# NT_SolarModule.net
KiCad netlist of a schematic drawn in EAGLE
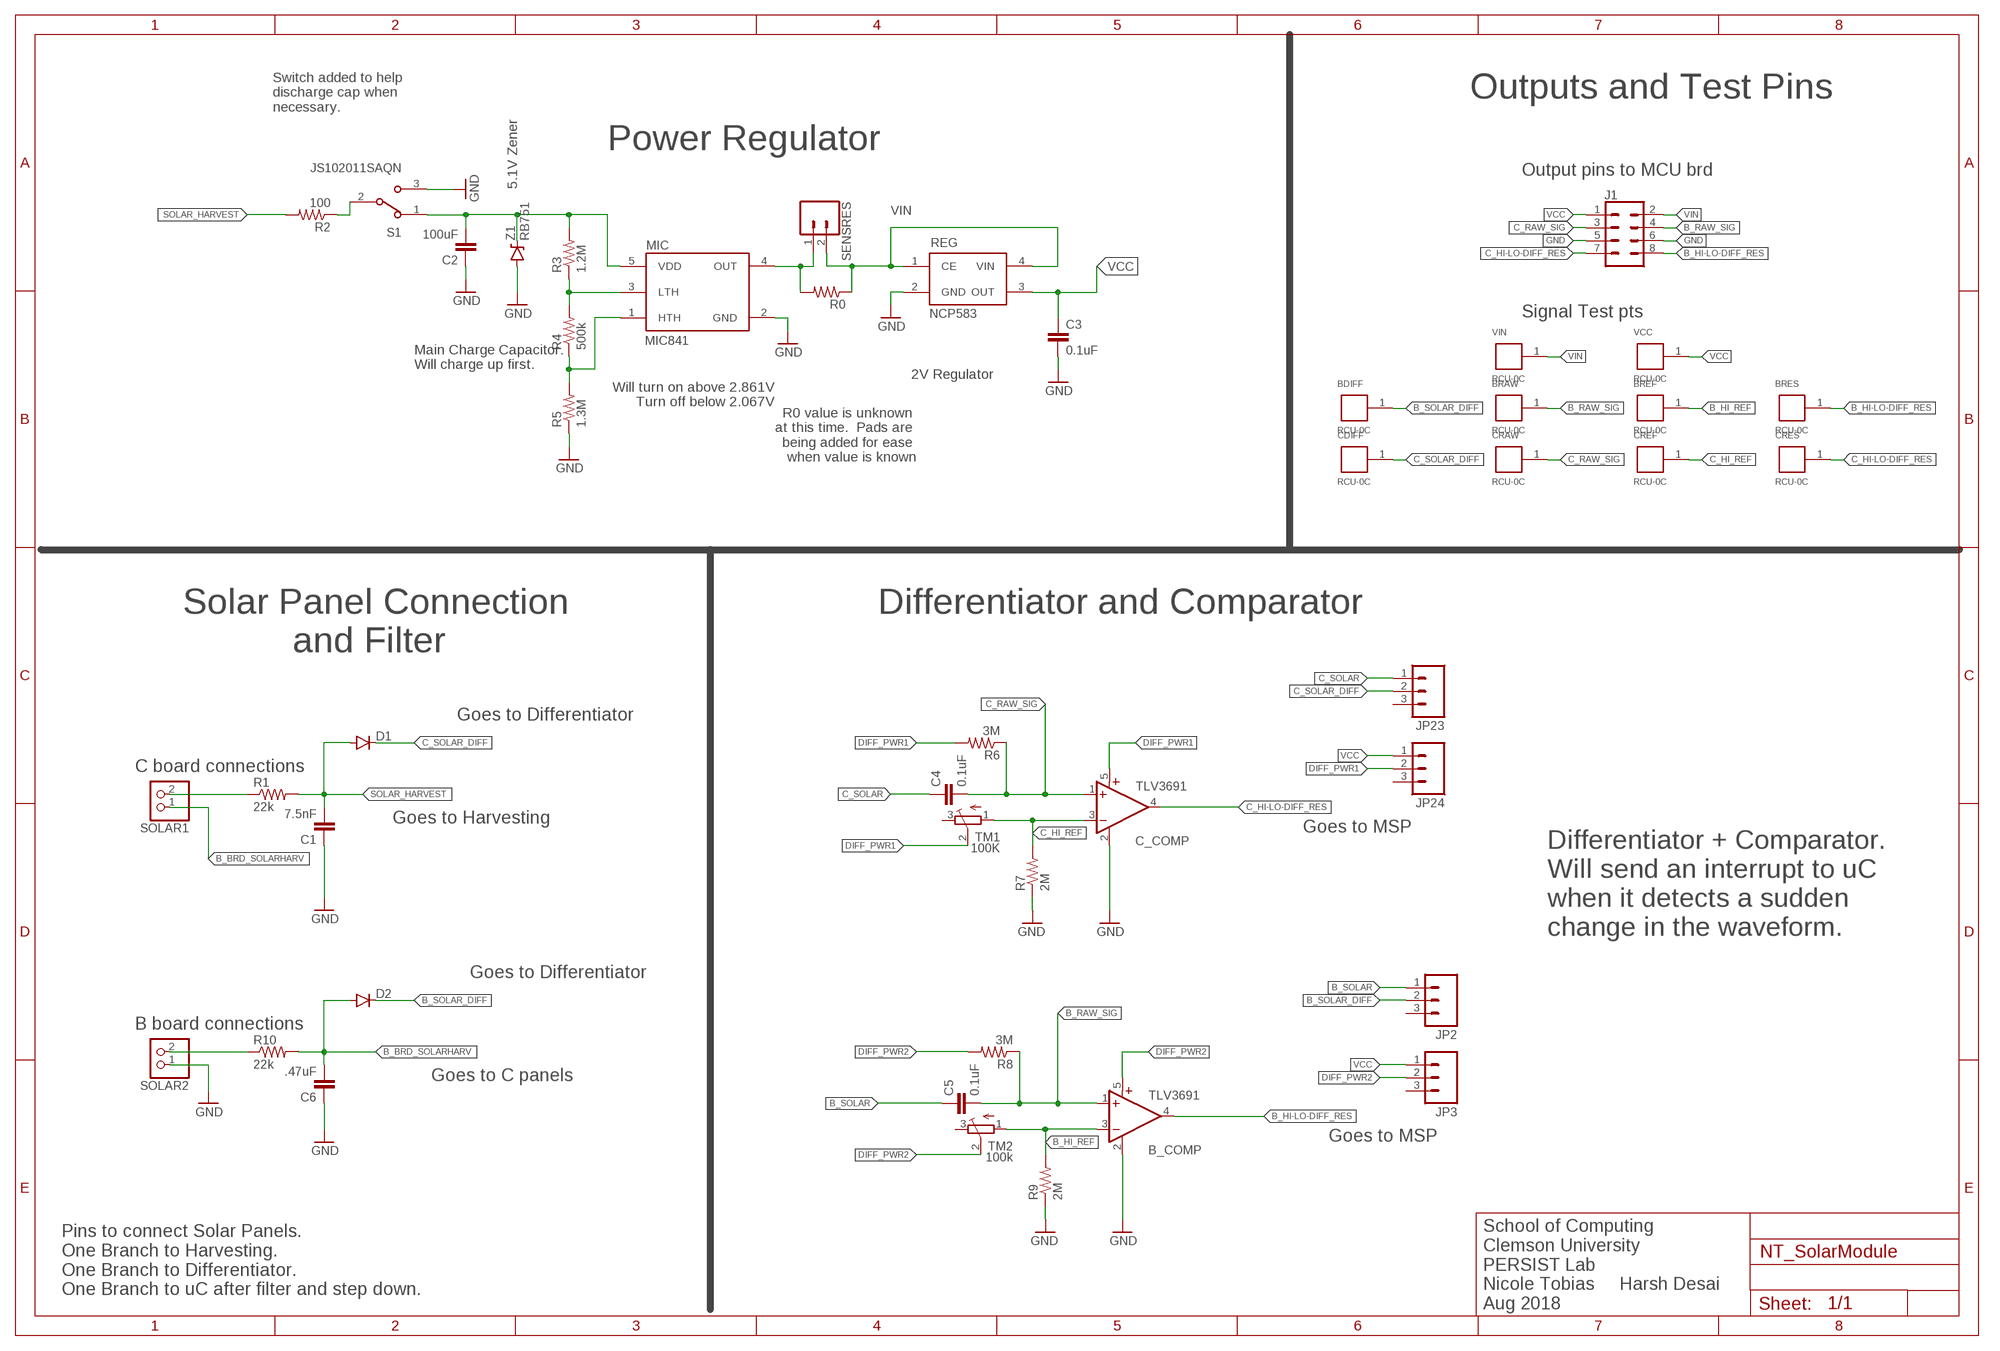
[diagram p0: schematic, sheet 1]

(export (version "E")
  (design (tool "Eeschema 10.0.6"))
  (components
    (comp (ref "BDIFF")
      (value "RCU-0C")
      (footprint "eagle-import:TE_RCU-0C")
      (fields
        (field (name "COMMENT") "RCU-0C _1625854-3_")
        (field (name "MF") "TE Connectivity")
        (field (name "TOLERANCE") "0%")
      )
      (libsource (lib "eagle-import") (part "RCU-0C"))
    )
    (comp (ref "BRAW")
      (value "RCU-0C")
      (footprint "eagle-import:TE_RCU-0C")
      (fields
        (field (name "COMMENT") "RCU-0C _1625854-3_")
        (field (name "MF") "TE Connectivity")
        (field (name "TOLERANCE") "0%")
      )
      (libsource (lib "eagle-import") (part "RCU-0C"))
    )
    (comp (ref "BREF")
      (value "RCU-0C")
      (footprint "eagle-import:TE_RCU-0C")
      (fields
        (field (name "COMMENT") "RCU-0C _1625854-3_")
        (field (name "MF") "TE Connectivity")
        (field (name "TOLERANCE") "0%")
      )
      (libsource (lib "eagle-import") (part "RCU-0C"))
    )
    (comp (ref "BRES")
      (value "RCU-0C")
      (footprint "eagle-import:TE_RCU-0C")
      (fields
        (field (name "COMMENT") "RCU-0C _1625854-3_")
        (field (name "MF") "TE Connectivity")
        (field (name "TOLERANCE") "0%")
      )
      (libsource (lib "eagle-import") (part "RCU-0C"))
    )
    (comp (ref "B_COMP")
      (value "TLV3691")
      (footprint "eagle-import:SC70-5")
      (libsource (lib "eagle-import") (part "TLV3691"))
    )
    (comp (ref "C1")
      (value "7.5nF")
      (footprint "eagle-import:0603-CAP")
      (libsource (lib "eagle-import") (part "CAP0603-CAP"))
    )
    (comp (ref "C2")
      (value "100uF")
      (footprint "eagle-import:0603-CAP")
      (libsource (lib "eagle-import") (part "CAP0603-CAP"))
    )
    (comp (ref "C3")
      (value "0.1uF")
      (footprint "eagle-import:0603-CAP")
      (libsource (lib "eagle-import") (part "CAP0603-CAP"))
    )
    (comp (ref "C4")
      (value "0.1uF")
      (footprint "eagle-import:0603-CAP")
      (libsource (lib "eagle-import") (part "CAP0603-CAP"))
    )
    (comp (ref "C5")
      (value "0.1uF")
      (footprint "eagle-import:0603-CAP")
      (libsource (lib "eagle-import") (part "CAP0603-CAP"))
    )
    (comp (ref "C6")
      (value ".47uF")
      (footprint "eagle-import:0603-CAP")
      (libsource (lib "eagle-import") (part "CAP0603-CAP"))
    )
    (comp (ref "CDIFF")
      (value "RCU-0C")
      (footprint "eagle-import:TE_RCU-0C")
      (fields
        (field (name "COMMENT") "RCU-0C _1625854-3_")
        (field (name "MF") "TE Connectivity")
        (field (name "TOLERANCE") "0%")
      )
      (libsource (lib "eagle-import") (part "RCU-0C"))
    )
    (comp (ref "CRAW")
      (value "RCU-0C")
      (footprint "eagle-import:TE_RCU-0C")
      (fields
        (field (name "COMMENT") "RCU-0C _1625854-3_")
        (field (name "MF") "TE Connectivity")
        (field (name "TOLERANCE") "0%")
      )
      (libsource (lib "eagle-import") (part "RCU-0C"))
    )
    (comp (ref "CREF")
      (value "RCU-0C")
      (footprint "eagle-import:TE_RCU-0C")
      (fields
        (field (name "COMMENT") "RCU-0C _1625854-3_")
        (field (name "MF") "TE Connectivity")
        (field (name "TOLERANCE") "0%")
      )
      (libsource (lib "eagle-import") (part "RCU-0C"))
    )
    (comp (ref "CRES")
      (value "RCU-0C")
      (footprint "eagle-import:TE_RCU-0C")
      (fields
        (field (name "COMMENT") "RCU-0C _1625854-3_")
        (field (name "MF") "TE Connectivity")
        (field (name "TOLERANCE") "0%")
      )
      (libsource (lib "eagle-import") (part "RCU-0C"))
    )
    (comp (ref "C_COMP")
      (value "TLV3691")
      (footprint "eagle-import:SC70-5")
      (libsource (lib "eagle-import") (part "TLV3691"))
    )
    (comp (ref "D1")
      (value "DIODESOD523")
      (footprint "eagle-import:SOD523")
      (libsource (lib "eagle-import") (part "DIODESOD523"))
    )
    (comp (ref "D2")
      (value "DIODESOD523")
      (footprint "eagle-import:SOD523")
      (libsource (lib "eagle-import") (part "DIODESOD523"))
    )
    (comp (ref "J1")
      (value "CONN_04X2")
      (footprint "eagle-import:2X4")
      (libsource (lib "eagle-import") (part "CONN_04X2"))
    )
    (comp (ref "JP2")
      (value "M03")
      (footprint "eagle-import:1X03-1.27MM")
      (libsource (lib "eagle-import") (part "M03"))
    )
    (comp (ref "JP3")
      (value "M03")
      (footprint "eagle-import:1X03-1.27MM")
      (libsource (lib "eagle-import") (part "M03"))
    )
    (comp (ref "JP23")
      (value "M03")
      (footprint "eagle-import:1X03-1.27MM")
      (libsource (lib "eagle-import") (part "M03"))
    )
    (comp (ref "JP24")
      (value "M03")
      (footprint "eagle-import:1X03-1.27MM")
      (libsource (lib "eagle-import") (part "M03"))
    )
    (comp (ref "MIC")
      (value "MIC841")
      (footprint "eagle-import:SC70-5")
      (libsource (lib "eagle-import") (part "MIC841"))
    )
    (comp (ref "R0")
      (value "RESISTOR0603")
      (footprint "eagle-import:0603-RES")
      (libsource (lib "eagle-import") (part "RESISTOR0603"))
    )
    (comp (ref "R1")
      (value "22k")
      (footprint "eagle-import:0603-RES")
      (libsource (lib "eagle-import") (part "RESISTOR0603"))
    )
    (comp (ref "R2")
      (value "100")
      (footprint "eagle-import:0603-RES")
      (libsource (lib "eagle-import") (part "RESISTOR0603"))
    )
    (comp (ref "R3")
      (value "1.2M")
      (footprint "eagle-import:0603-RES")
      (libsource (lib "eagle-import") (part "RESISTOR0603"))
    )
    (comp (ref "R4")
      (value "500k")
      (footprint "eagle-import:0603-RES")
      (libsource (lib "eagle-import") (part "RESISTOR0603"))
    )
    (comp (ref "R5")
      (value "1.3M")
      (footprint "eagle-import:0603-RES")
      (libsource (lib "eagle-import") (part "RESISTOR0603"))
    )
    (comp (ref "R6")
      (value "3M")
      (footprint "eagle-import:0603-RES")
      (libsource (lib "eagle-import") (part "RESISTOR0603"))
    )
    (comp (ref "R7")
      (value "2M")
      (footprint "eagle-import:0603-RES")
      (libsource (lib "eagle-import") (part "RESISTOR0603"))
    )
    (comp (ref "R8")
      (value "3M")
      (footprint "eagle-import:0603-RES")
      (libsource (lib "eagle-import") (part "RESISTOR0603"))
    )
    (comp (ref "R9")
      (value "2M")
      (footprint "eagle-import:0603-RES")
      (libsource (lib "eagle-import") (part "RESISTOR0603"))
    )
    (comp (ref "R10")
      (value "22k")
      (footprint "eagle-import:0603-RES")
      (libsource (lib "eagle-import") (part "RESISTOR0603"))
    )
    (comp (ref "REG")
      (value "NCP583")
      (footprint "eagle-import:SC82-AB_1PRIMARY")
      (libsource (lib "eagle-import") (part "NCP583"))
    )
    (comp (ref "S1")
      (value "JS102011SAQN")
      (footprint "eagle-import:SW_JS102011SAQN")
      (fields (field (name "MF") "C&K Components"))
      (libsource (lib "eagle-import") (part "JS102011SAQN"))
    )
    (comp (ref "SENSRES")
      (value "CONN_02")
      (footprint "eagle-import:1X02")
      (libsource (lib "eagle-import") (part "CONN_02"))
    )
    (comp (ref "SOLAR1")
      (value "PINHD-1X2")
      (footprint "eagle-import:1X02")
      (libsource (lib "eagle-import") (part "PINHD-1X2"))
    )
    (comp (ref "SOLAR2")
      (value "PINHD-1X2")
      (footprint "eagle-import:1X02")
      (libsource (lib "eagle-import") (part "PINHD-1X2"))
    )
    (comp (ref "TM1")
      (value "100K")
      (footprint "eagle-import:TC33X")
      (libsource (lib "eagle-import") (part "TRIMPOTTC33X"))
    )
    (comp (ref "TM2")
      (value "100k")
      (footprint "eagle-import:TC33X")
      (libsource (lib "eagle-import") (part "TRIMPOTTC33X"))
    )
    (comp (ref "VCC")
      (value "RCU-0C")
      (footprint "eagle-import:TE_RCU-0C")
      (fields
        (field (name "COMMENT") "RCU-0C _1625854-3_")
        (field (name "MF") "TE Connectivity")
        (field (name "TOLERANCE") "0%")
      )
      (libsource (lib "eagle-import") (part "RCU-0C"))
    )
    (comp (ref "VIN")
      (value "RCU-0C")
      (footprint "eagle-import:TE_RCU-0C")
      (fields
        (field (name "COMMENT") "RCU-0C _1625854-3_")
        (field (name "MF") "TE Connectivity")
        (field (name "TOLERANCE") "0%")
      )
      (libsource (lib "eagle-import") (part "RCU-0C"))
    )
    (comp (ref "Z1")
      (value "RB751")
      (footprint "eagle-import:SOD-523")
      (libsource (lib "eagle-import") (part "DIODE-ZENER"))
    )
  )
  (nets
    (net (code "1") (name "B_BRD_SOLARHARV") (class "Default")
      (node (ref "C6") (pin "2") (pinfunction "2_2") (pintype "passive"))
      (node (ref "D2") (pin "A") (pinfunction "A_A") (pintype "passive"))
      (node (ref "R10") (pin "2") (pinfunction "2_2") (pintype "passive"))
      (node (ref "SOLAR1") (pin "1") (pinfunction "1_1") (pintype "passive"))
    )
    (net (code "2") (name "B_HI-LO-DIFF_RES") (class "Default")
      (node (ref "BRES") (pin "1") (pinfunction "1_1") (pintype "passive"))
      (node (ref "B_COMP") (pin "4") (pinfunction "OUT_4") (pintype "output"))
      (node (ref "J1") (pin "8") (pinfunction "8_8") (pintype "passive"))
    )
    (net (code "3") (name "B_HI_REF") (class "Default")
      (node (ref "BREF") (pin "1") (pinfunction "1_1") (pintype "passive"))
      (node (ref "B_COMP") (pin "3") (pinfunction "-IN_3") (pintype "input"))
      (node (ref "R9") (pin "2") (pinfunction "2_2") (pintype "passive"))
      (node (ref "TM2") (pin "1") (pinfunction "A_1") (pintype "passive"))
    )
    (net (code "4") (name "B_RAW_SIG") (class "Default")
      (node (ref "BRAW") (pin "1") (pinfunction "1_1") (pintype "passive"))
      (node (ref "B_COMP") (pin "1") (pinfunction "+IN_1") (pintype "input"))
      (node (ref "C5") (pin "2") (pinfunction "2_2") (pintype "passive"))
      (node (ref "J1") (pin "4") (pinfunction "4_4") (pintype "passive"))
      (node (ref "R8") (pin "1") (pinfunction "1_1") (pintype "passive"))
    )
    (net (code "5") (name "B_SOLAR") (class "Default")
      (node (ref "C5") (pin "1") (pinfunction "1_1") (pintype "passive"))
      (node (ref "JP2") (pin "1") (pinfunction "1_1") (pintype "passive"))
    )
    (net (code "6") (name "B_SOLAR_DIFF") (class "Default")
      (node (ref "BDIFF") (pin "1") (pinfunction "1_1") (pintype "passive"))
      (node (ref "D2") (pin "C") (pinfunction "C_C") (pintype "passive"))
      (node (ref "JP2") (pin "2") (pinfunction "2_2") (pintype "passive"))
    )
    (net (code "7") (name "C_HI-LO-DIFF_RES") (class "Default")
      (node (ref "CRES") (pin "1") (pinfunction "1_1") (pintype "passive"))
      (node (ref "C_COMP") (pin "4") (pinfunction "OUT_4") (pintype "output"))
      (node (ref "J1") (pin "7") (pinfunction "7_7") (pintype "passive"))
    )
    (net (code "8") (name "C_HI_REF") (class "Default")
      (node (ref "CREF") (pin "1") (pinfunction "1_1") (pintype "passive"))
      (node (ref "C_COMP") (pin "3") (pinfunction "-IN_3") (pintype "input"))
      (node (ref "R7") (pin "2") (pinfunction "2_2") (pintype "passive"))
      (node (ref "TM1") (pin "1") (pinfunction "A_1") (pintype "passive"))
    )
    (net (code "9") (name "C_RAW_SIG") (class "Default")
      (node (ref "C4") (pin "2") (pinfunction "2_2") (pintype "passive"))
      (node (ref "CRAW") (pin "1") (pinfunction "1_1") (pintype "passive"))
      (node (ref "C_COMP") (pin "1") (pinfunction "+IN_1") (pintype "input"))
      (node (ref "J1") (pin "3") (pinfunction "3_3") (pintype "passive"))
      (node (ref "R6") (pin "1") (pinfunction "1_1") (pintype "passive"))
    )
    (net (code "10") (name "C_SOLAR") (class "Default")
      (node (ref "C4") (pin "1") (pinfunction "1_1") (pintype "passive"))
      (node (ref "JP23") (pin "1") (pinfunction "1_1") (pintype "passive"))
    )
    (net (code "11") (name "C_SOLAR_DIFF") (class "Default")
      (node (ref "CDIFF") (pin "1") (pinfunction "1_1") (pintype "passive"))
      (node (ref "D1") (pin "C") (pinfunction "C_C") (pintype "passive"))
      (node (ref "JP23") (pin "2") (pinfunction "2_2") (pintype "passive"))
    )
    (net (code "12") (name "DIFF_PWR1") (class "Default")
      (node (ref "C_COMP") (pin "5") (pinfunction "V+_5") (pintype "power_in"))
      (node (ref "JP24") (pin "2") (pinfunction "2_2") (pintype "passive"))
      (node (ref "R6") (pin "2") (pinfunction "2_2") (pintype "passive"))
      (node (ref "TM1") (pin "2") (pinfunction "S_2") (pintype "passive"))
    )
    (net (code "13") (name "DIFF_PWR2") (class "Default")
      (node (ref "B_COMP") (pin "5") (pinfunction "V+_5") (pintype "power_in"))
      (node (ref "JP3") (pin "2") (pinfunction "2_2") (pintype "passive"))
      (node (ref "R8") (pin "2") (pinfunction "2_2") (pintype "passive"))
      (node (ref "TM2") (pin "2") (pinfunction "S_2") (pintype "passive"))
    )
    (net (code "14") (name "GND") (class "Default")
      (node (ref "B_COMP") (pin "2") (pinfunction "GND_2") (pintype "power_in"))
      (node (ref "C1") (pin "1") (pinfunction "1_1") (pintype "passive"))
      (node (ref "C2") (pin "1") (pinfunction "1_1") (pintype "passive"))
      (node (ref "C3") (pin "2") (pinfunction "2_2") (pintype "passive"))
      (node (ref "C6") (pin "1") (pinfunction "1_1") (pintype "passive"))
      (node (ref "C_COMP") (pin "2") (pinfunction "GND_2") (pintype "power_in"))
      (node (ref "J1") (pin "5") (pinfunction "5_5") (pintype "passive"))
      (node (ref "J1") (pin "6") (pinfunction "6_6") (pintype "passive"))
      (node (ref "MIC") (pin "2") (pinfunction "GND_2") (pintype "bidirectional"))
      (node (ref "R5") (pin "1") (pinfunction "1_1") (pintype "passive"))
      (node (ref "R7") (pin "1") (pinfunction "1_1") (pintype "passive"))
      (node (ref "R9") (pin "1") (pinfunction "1_1") (pintype "passive"))
      (node (ref "REG") (pin "2") (pinfunction "GND_2") (pintype "bidirectional"))
      (node (ref "S1") (pin "3") (pinfunction "3_3") (pintype "passive"))
      (node (ref "SOLAR2") (pin "1") (pinfunction "1_1") (pintype "passive"))
      (node (ref "Z1") (pin "ANODE") (pinfunction "A_ANODE") (pintype "passive"))
    )
    (net (code "15") (name "Net-(MIC-HTH)") (class "Default")
      (node (ref "MIC") (pin "1") (pinfunction "HTH_1") (pintype "bidirectional"))
      (node (ref "R4") (pin "1") (pinfunction "1_1") (pintype "passive"))
      (node (ref "R5") (pin "2") (pinfunction "2_2") (pintype "passive"))
    )
    (net (code "16") (name "Net-(MIC-LTH)") (class "Default")
      (node (ref "MIC") (pin "3") (pinfunction "LTH_3") (pintype "bidirectional"))
      (node (ref "R3") (pin "1") (pinfunction "1_1") (pintype "passive"))
      (node (ref "R4") (pin "2") (pinfunction "2_2") (pintype "passive"))
    )
    (net (code "17") (name "Net-(MIC-OUT)") (class "Default")
      (node (ref "MIC") (pin "4") (pinfunction "OUT_4") (pintype "bidirectional"))
      (node (ref "R0") (pin "2") (pinfunction "2_2") (pintype "passive"))
      (node (ref "SENSRES") (pin "1") (pinfunction "1_1") (pintype "passive"))
    )
    (net (code "18") (name "Net-(MIC-VDD)") (class "Default")
      (node (ref "C2") (pin "2") (pinfunction "2_2") (pintype "passive"))
      (node (ref "MIC") (pin "5") (pinfunction "VDD_5") (pintype "bidirectional"))
      (node (ref "R3") (pin "2") (pinfunction "2_2") (pintype "passive"))
      (node (ref "S1") (pin "1") (pinfunction "1_1") (pintype "passive"))
      (node (ref "Z1") (pin "CATHODE") (pinfunction "C_CATHODE") (pintype "passive"))
    )
    (net (code "19") (name "Net-(R1-Pad1)") (class "Default")
      (node (ref "R1") (pin "1") (pinfunction "1_1") (pintype "passive"))
      (node (ref "SOLAR1") (pin "2") (pinfunction "2_2") (pintype "passive"))
    )
    (net (code "20") (name "Net-(R2-Pad1)") (class "Default")
      (node (ref "R2") (pin "1") (pinfunction "1_1") (pintype "passive"))
      (node (ref "S1") (pin "2") (pinfunction "2_2") (pintype "passive"))
    )
    (net (code "21") (name "Net-(R10-Pad1)") (class "Default")
      (node (ref "R10") (pin "1") (pinfunction "1_1") (pintype "passive"))
      (node (ref "SOLAR2") (pin "2") (pinfunction "2_2") (pintype "passive"))
    )
    (net (code "22") (name "SOLAR_HARVEST") (class "Default")
      (node (ref "C1") (pin "2") (pinfunction "2_2") (pintype "passive"))
      (node (ref "D1") (pin "A") (pinfunction "A_A") (pintype "passive"))
      (node (ref "R1") (pin "2") (pinfunction "2_2") (pintype "passive"))
      (node (ref "R2") (pin "2") (pinfunction "2_2") (pintype "passive"))
    )
    (net (code "23") (name "VCC") (class "Default")
      (node (ref "C3") (pin "1") (pinfunction "1_1") (pintype "passive"))
      (node (ref "J1") (pin "1") (pinfunction "1_1") (pintype "passive"))
      (node (ref "JP24") (pin "1") (pinfunction "1_1") (pintype "passive"))
      (node (ref "JP3") (pin "1") (pinfunction "1_1") (pintype "passive"))
      (node (ref "REG") (pin "3") (pinfunction "OUT_3") (pintype "bidirectional"))
      (node (ref "VCC") (pin "1") (pinfunction "1_1") (pintype "passive"))
    )
    (net (code "24") (name "VIN") (class "Default")
      (node (ref "J1") (pin "2") (pinfunction "2_2") (pintype "passive"))
      (node (ref "R0") (pin "1") (pinfunction "1_1") (pintype "passive"))
      (node (ref "REG") (pin "1") (pinfunction "CE_1") (pintype "bidirectional"))
      (node (ref "REG") (pin "4") (pinfunction "VIN_4") (pintype "bidirectional"))
      (node (ref "SENSRES") (pin "2") (pinfunction "2_2") (pintype "passive"))
      (node (ref "VIN") (pin "1") (pinfunction "1_1") (pintype "passive"))
    )
    (net (code "25") (name "unconnected-(JP2-Pad3)") (class "Default")
      (node (ref "JP2") (pin "3") (pinfunction "3_3") (pintype "passive"))
    )
    (net (code "26") (name "unconnected-(JP3-Pad3)") (class "Default")
      (node (ref "JP3") (pin "3") (pinfunction "3_3") (pintype "passive"))
    )
    (net (code "27") (name "unconnected-(JP23-Pad3)") (class "Default")
      (node (ref "JP23") (pin "3") (pinfunction "3_3") (pintype "passive"))
    )
    (net (code "28") (name "unconnected-(JP24-Pad3)") (class "Default")
      (node (ref "JP24") (pin "3") (pinfunction "3_3") (pintype "passive"))
    )
    (net (code "29") (name "unconnected-(TM1-E-Pad3)") (class "Default")
      (node (ref "TM1") (pin "3") (pinfunction "E_3") (pintype "passive"))
    )
    (net (code "30") (name "unconnected-(TM2-E-Pad3)") (class "Default")
      (node (ref "TM2") (pin "3") (pinfunction "E_3") (pintype "passive"))
    )
  )
)
